# Ionic_Skin_Sensorized_Glove.net
KiCad netlist of a schematic drawn in EAGLE
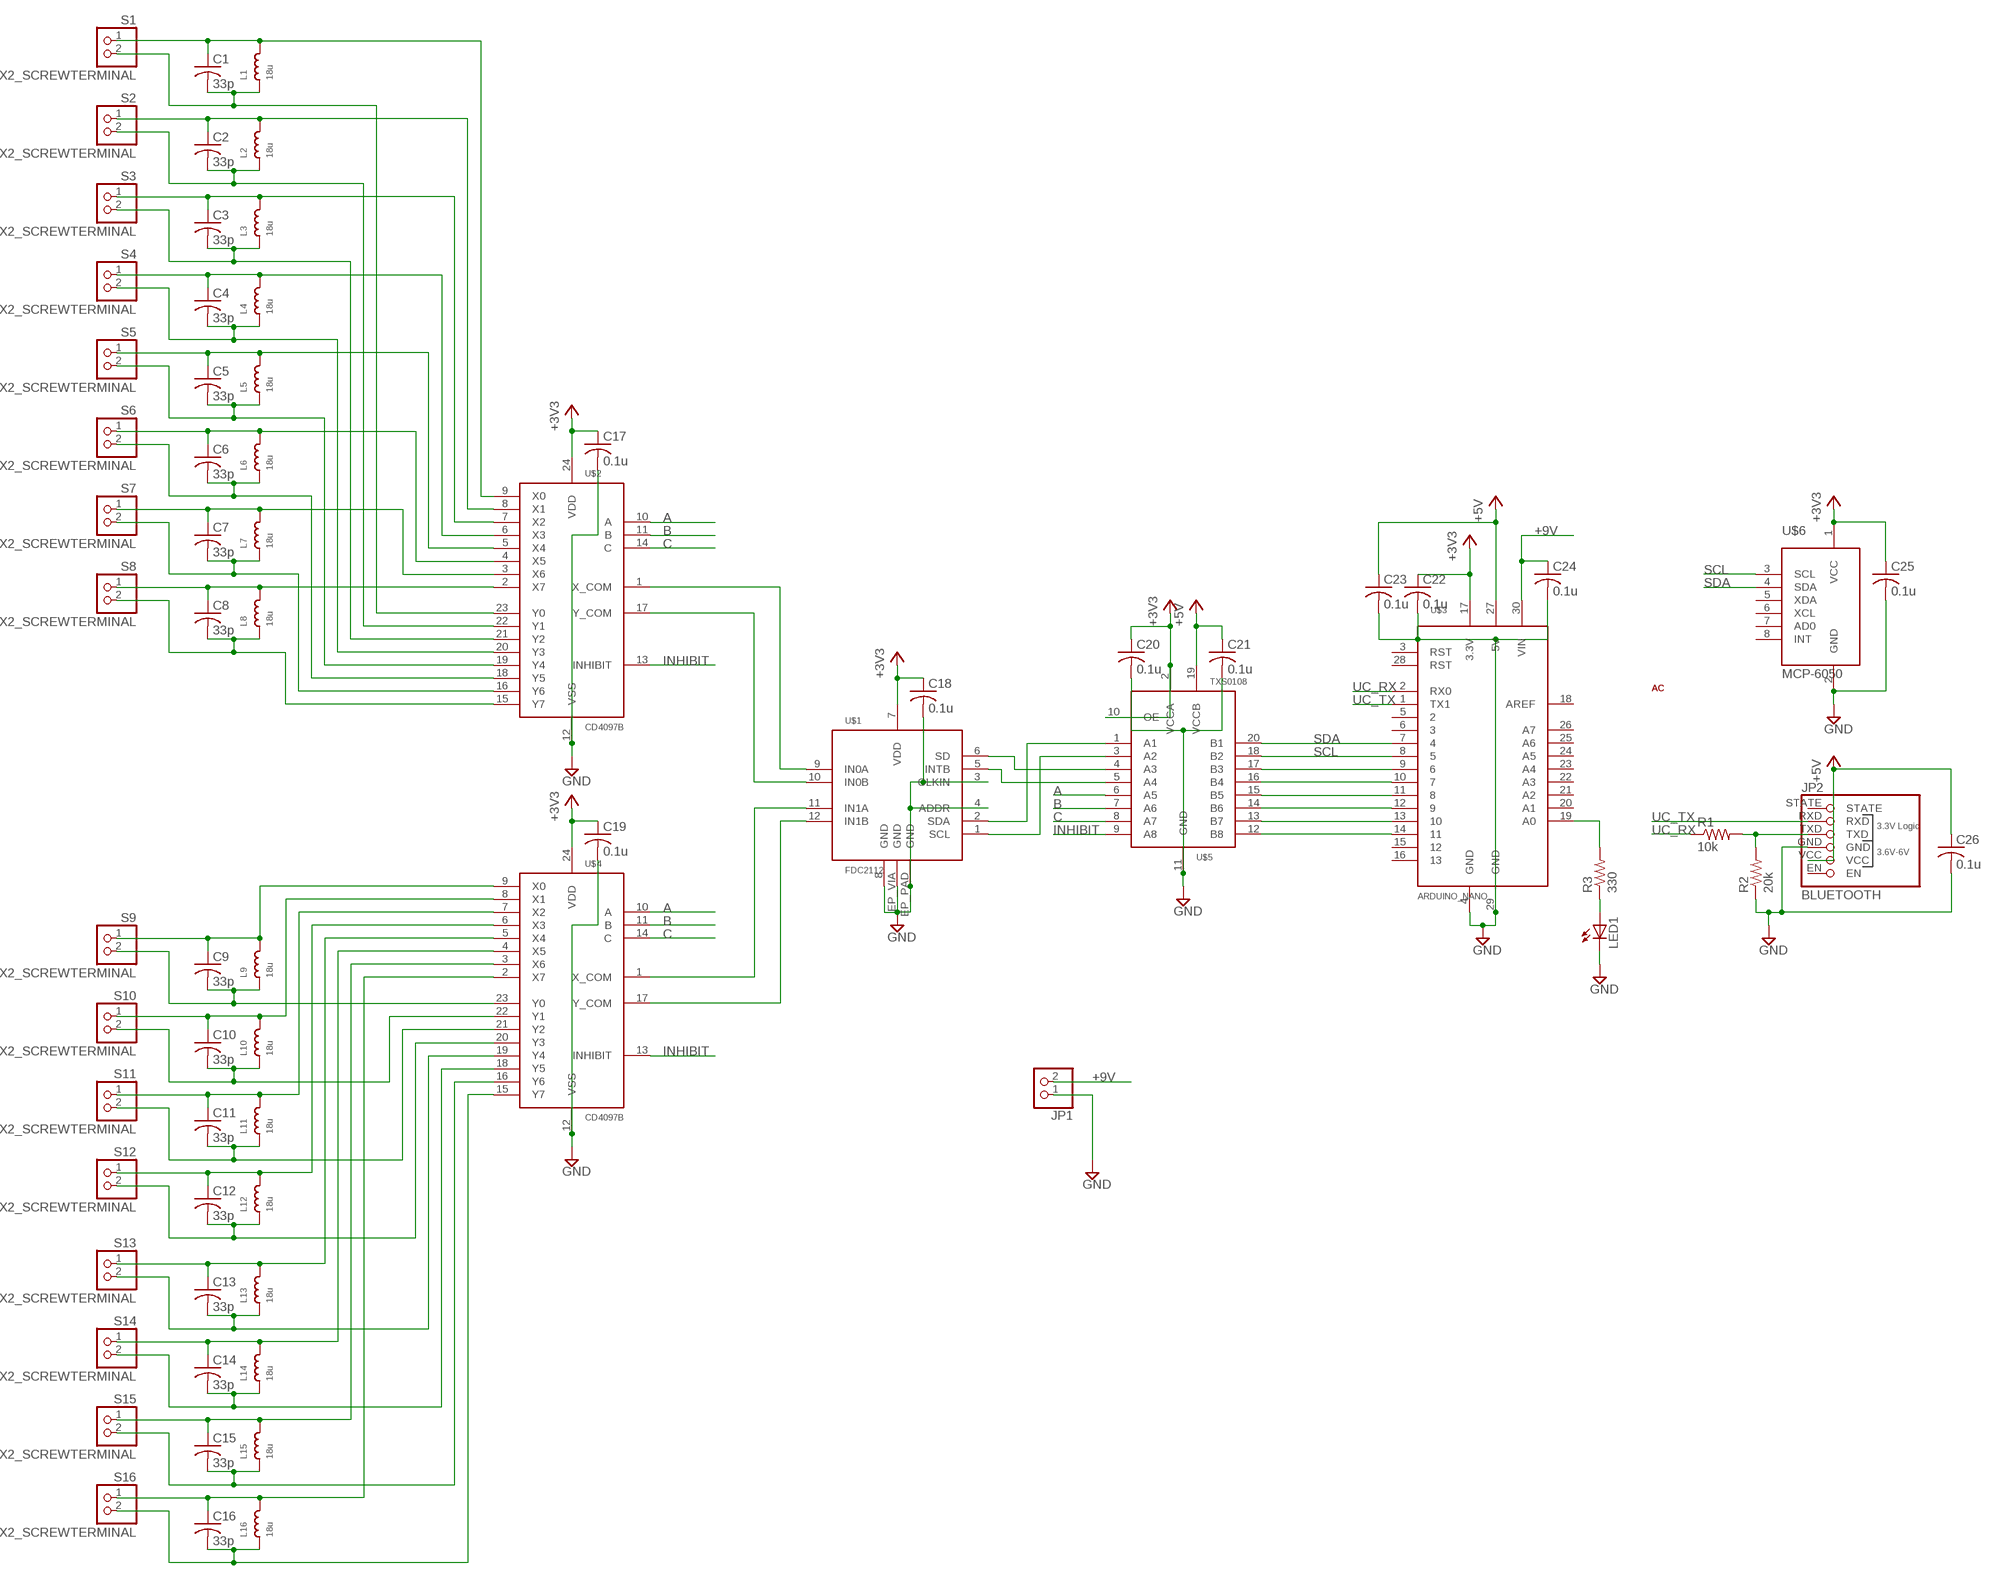
[diagram p0: schematic, sheet 1]

(export (version "E")
  (design (tool "Eeschema 10.0.6"))
  (components
    (comp (ref "C1")
      (value "33p")
      (footprint "eagle-import:C0805")
      (libsource (lib "eagle-import") (part "C-USC0805"))
    )
    (comp (ref "C2")
      (value "33p")
      (footprint "eagle-import:C0805")
      (libsource (lib "eagle-import") (part "C-USC0805"))
    )
    (comp (ref "C3")
      (value "33p")
      (footprint "eagle-import:C0805")
      (libsource (lib "eagle-import") (part "C-USC0805"))
    )
    (comp (ref "C4")
      (value "33p")
      (footprint "eagle-import:C0805")
      (libsource (lib "eagle-import") (part "C-USC0805"))
    )
    (comp (ref "C5")
      (value "33p")
      (footprint "eagle-import:C0805")
      (libsource (lib "eagle-import") (part "C-USC0805"))
    )
    (comp (ref "C6")
      (value "33p")
      (footprint "eagle-import:C0805")
      (libsource (lib "eagle-import") (part "C-USC0805"))
    )
    (comp (ref "C7")
      (value "33p")
      (footprint "eagle-import:C0805")
      (libsource (lib "eagle-import") (part "C-USC0805"))
    )
    (comp (ref "C8")
      (value "33p")
      (footprint "eagle-import:C0805")
      (libsource (lib "eagle-import") (part "C-USC0805"))
    )
    (comp (ref "C9")
      (value "33p")
      (footprint "eagle-import:C0805")
      (libsource (lib "eagle-import") (part "C-USC0805"))
    )
    (comp (ref "C10")
      (value "33p")
      (footprint "eagle-import:C0805")
      (libsource (lib "eagle-import") (part "C-USC0805"))
    )
    (comp (ref "C11")
      (value "33p")
      (footprint "eagle-import:C0805")
      (libsource (lib "eagle-import") (part "C-USC0805"))
    )
    (comp (ref "C12")
      (value "33p")
      (footprint "eagle-import:C0805")
      (libsource (lib "eagle-import") (part "C-USC0805"))
    )
    (comp (ref "C13")
      (value "33p")
      (footprint "eagle-import:C0805")
      (libsource (lib "eagle-import") (part "C-USC0805"))
    )
    (comp (ref "C14")
      (value "33p")
      (footprint "eagle-import:C0805")
      (libsource (lib "eagle-import") (part "C-USC0805"))
    )
    (comp (ref "C15")
      (value "33p")
      (footprint "eagle-import:C0805")
      (libsource (lib "eagle-import") (part "C-USC0805"))
    )
    (comp (ref "C16")
      (value "33p")
      (footprint "eagle-import:C0805")
      (libsource (lib "eagle-import") (part "C-USC0805"))
    )
    (comp (ref "C17")
      (value "0.1u")
      (footprint "eagle-import:C0805")
      (libsource (lib "eagle-import") (part "C-USC0805"))
    )
    (comp (ref "C18")
      (value "0.1u")
      (footprint "eagle-import:C0805")
      (libsource (lib "eagle-import") (part "C-USC0805"))
    )
    (comp (ref "C19")
      (value "0.1u")
      (footprint "eagle-import:C0805")
      (libsource (lib "eagle-import") (part "C-USC0805"))
    )
    (comp (ref "C20")
      (value "0.1u")
      (footprint "eagle-import:C0805")
      (libsource (lib "eagle-import") (part "C-USC0805"))
    )
    (comp (ref "C21")
      (value "0.1u")
      (footprint "eagle-import:C0805")
      (libsource (lib "eagle-import") (part "C-USC0805"))
    )
    (comp (ref "C22")
      (value "0.1u")
      (footprint "eagle-import:C0805")
      (libsource (lib "eagle-import") (part "C-USC0805"))
    )
    (comp (ref "C23")
      (value "0.1u")
      (footprint "eagle-import:C0805")
      (libsource (lib "eagle-import") (part "C-USC0805"))
    )
    (comp (ref "C24")
      (value "0.1u")
      (footprint "eagle-import:C0805")
      (libsource (lib "eagle-import") (part "C-USC0805"))
    )
    (comp (ref "C25")
      (value "0.1u")
      (footprint "eagle-import:C0805")
      (libsource (lib "eagle-import") (part "C-USC0805"))
    )
    (comp (ref "C26")
      (value "0.1u")
      (footprint "eagle-import:C0805")
      (libsource (lib "eagle-import") (part "C-USC0805"))
    )
    (comp (ref "JP1")
      (value "PINHD-1X2")
      (footprint "eagle-import:1X02")
      (libsource (lib "eagle-import") (part "PINHD-1X2"))
    )
    (comp (ref "JP2")
      (value "BLUETOOTH")
      (footprint "eagle-import:HC-06")
      (libsource (lib "eagle-import") (part "HC-06"))
    )
    (comp (ref "L1")
      (value "18u")
      (footprint "eagle-import:_0805MP")
      (libsource (lib "eagle-import") (part "INDUCTOR_0805MP"))
    )
    (comp (ref "L2")
      (value "18u")
      (footprint "eagle-import:_0805MP")
      (libsource (lib "eagle-import") (part "INDUCTOR_0805MP"))
    )
    (comp (ref "L3")
      (value "18u")
      (footprint "eagle-import:_0805MP")
      (libsource (lib "eagle-import") (part "INDUCTOR_0805MP"))
    )
    (comp (ref "L4")
      (value "18u")
      (footprint "eagle-import:_0805MP")
      (libsource (lib "eagle-import") (part "INDUCTOR_0805MP"))
    )
    (comp (ref "L5")
      (value "18u")
      (footprint "eagle-import:_0805MP")
      (libsource (lib "eagle-import") (part "INDUCTOR_0805MP"))
    )
    (comp (ref "L6")
      (value "18u")
      (footprint "eagle-import:_0805MP")
      (libsource (lib "eagle-import") (part "INDUCTOR_0805MP"))
    )
    (comp (ref "L7")
      (value "18u")
      (footprint "eagle-import:_0805MP")
      (libsource (lib "eagle-import") (part "INDUCTOR_0805MP"))
    )
    (comp (ref "L8")
      (value "18u")
      (footprint "eagle-import:_0805MP")
      (libsource (lib "eagle-import") (part "INDUCTOR_0805MP"))
    )
    (comp (ref "L9")
      (value "18u")
      (footprint "eagle-import:_0805MP")
      (libsource (lib "eagle-import") (part "INDUCTOR_0805MP"))
    )
    (comp (ref "L10")
      (value "18u")
      (footprint "eagle-import:_0805MP")
      (libsource (lib "eagle-import") (part "INDUCTOR_0805MP"))
    )
    (comp (ref "L11")
      (value "18u")
      (footprint "eagle-import:_0805MP")
      (libsource (lib "eagle-import") (part "INDUCTOR_0805MP"))
    )
    (comp (ref "L12")
      (value "18u")
      (footprint "eagle-import:_0805MP")
      (libsource (lib "eagle-import") (part "INDUCTOR_0805MP"))
    )
    (comp (ref "L13")
      (value "18u")
      (footprint "eagle-import:_0805MP")
      (libsource (lib "eagle-import") (part "INDUCTOR_0805MP"))
    )
    (comp (ref "L14")
      (value "18u")
      (footprint "eagle-import:_0805MP")
      (libsource (lib "eagle-import") (part "INDUCTOR_0805MP"))
    )
    (comp (ref "L15")
      (value "18u")
      (footprint "eagle-import:_0805MP")
      (libsource (lib "eagle-import") (part "INDUCTOR_0805MP"))
    )
    (comp (ref "L16")
      (value "18u")
      (footprint "eagle-import:_0805MP")
      (libsource (lib "eagle-import") (part "INDUCTOR_0805MP"))
    )
    (comp (ref "LED1")
      (value "LEDCHIPLED_0805")
      (footprint "eagle-import:CHIPLED_0805")
      (libsource (lib "eagle-import") (part "LEDCHIPLED_0805"))
    )
    (comp (ref "R1")
      (value "10k")
      (footprint "eagle-import:R0805")
      (libsource (lib "eagle-import") (part "R-US_R0805"))
    )
    (comp (ref "R2")
      (value "20k")
      (footprint "eagle-import:R0805")
      (libsource (lib "eagle-import") (part "R-US_R0805"))
    )
    (comp (ref "R3")
      (value "330")
      (footprint "eagle-import:R0805")
      (libsource (lib "eagle-import") (part "R-US_R0805"))
    )
    (comp (ref "S1")
      (value "1X2_SCREWTERMINAL")
      (footprint "eagle-import:1X2-2.54MM")
      (libsource (lib "eagle-import") (part "1X2_SCREWTERMINAL"))
    )
    (comp (ref "S2")
      (value "1X2_SCREWTERMINAL")
      (footprint "eagle-import:1X2-2.54MM")
      (libsource (lib "eagle-import") (part "1X2_SCREWTERMINAL"))
    )
    (comp (ref "S3")
      (value "1X2_SCREWTERMINAL")
      (footprint "eagle-import:1X2-2.54MM")
      (libsource (lib "eagle-import") (part "1X2_SCREWTERMINAL"))
    )
    (comp (ref "S4")
      (value "1X2_SCREWTERMINAL")
      (footprint "eagle-import:1X2-2.54MM")
      (libsource (lib "eagle-import") (part "1X2_SCREWTERMINAL"))
    )
    (comp (ref "S5")
      (value "1X2_SCREWTERMINAL")
      (footprint "eagle-import:1X2-2.54MM")
      (libsource (lib "eagle-import") (part "1X2_SCREWTERMINAL"))
    )
    (comp (ref "S6")
      (value "1X2_SCREWTERMINAL")
      (footprint "eagle-import:1X2-2.54MM")
      (libsource (lib "eagle-import") (part "1X2_SCREWTERMINAL"))
    )
    (comp (ref "S7")
      (value "1X2_SCREWTERMINAL")
      (footprint "eagle-import:1X2-2.54MM")
      (libsource (lib "eagle-import") (part "1X2_SCREWTERMINAL"))
    )
    (comp (ref "S8")
      (value "1X2_SCREWTERMINAL")
      (footprint "eagle-import:1X2-2.54MM")
      (libsource (lib "eagle-import") (part "1X2_SCREWTERMINAL"))
    )
    (comp (ref "S9")
      (value "1X2_SCREWTERMINAL")
      (footprint "eagle-import:1X2-2.54MM")
      (libsource (lib "eagle-import") (part "1X2_SCREWTERMINAL"))
    )
    (comp (ref "S10")
      (value "1X2_SCREWTERMINAL")
      (footprint "eagle-import:1X2-2.54MM")
      (libsource (lib "eagle-import") (part "1X2_SCREWTERMINAL"))
    )
    (comp (ref "S11")
      (value "1X2_SCREWTERMINAL")
      (footprint "eagle-import:1X2-2.54MM")
      (libsource (lib "eagle-import") (part "1X2_SCREWTERMINAL"))
    )
    (comp (ref "S12")
      (value "1X2_SCREWTERMINAL")
      (footprint "eagle-import:1X2-2.54MM")
      (libsource (lib "eagle-import") (part "1X2_SCREWTERMINAL"))
    )
    (comp (ref "S13")
      (value "1X2_SCREWTERMINAL")
      (footprint "eagle-import:1X2-2.54MM")
      (libsource (lib "eagle-import") (part "1X2_SCREWTERMINAL"))
    )
    (comp (ref "S14")
      (value "1X2_SCREWTERMINAL")
      (footprint "eagle-import:1X2-2.54MM")
      (libsource (lib "eagle-import") (part "1X2_SCREWTERMINAL"))
    )
    (comp (ref "S15")
      (value "1X2_SCREWTERMINAL")
      (footprint "eagle-import:1X2-2.54MM")
      (libsource (lib "eagle-import") (part "1X2_SCREWTERMINAL"))
    )
    (comp (ref "S16")
      (value "1X2_SCREWTERMINAL")
      (footprint "eagle-import:1X2-2.54MM")
      (libsource (lib "eagle-import") (part "1X2_SCREWTERMINAL"))
    )
    (comp (ref "U$1")
      (value "FDC2112")
      (footprint "eagle-import:WSON-12")
      (libsource (lib "eagle-import") (part "FDC2112"))
    )
    (comp (ref "U$2")
      (value "CD4097B")
      (footprint "eagle-import:TSSOP-24")
      (libsource (lib "eagle-import") (part "CD4097B"))
    )
    (comp (ref "U$3")
      (value "ARDUINO_NANO")
      (footprint "eagle-import:ARDUINO_NANO")
      (libsource (lib "eagle-import") (part "ARDUINO_NANO"))
    )
    (comp (ref "U$4")
      (value "CD4097B")
      (footprint "eagle-import:TSSOP-24")
      (libsource (lib "eagle-import") (part "CD4097B"))
    )
    (comp (ref "U$5")
      (value "TXS0108")
      (footprint "eagle-import:TSSOP-20")
      (libsource (lib "eagle-import") (part "TXS0108"))
    )
    (comp (ref "U$6")
      (value "MCP-6050")
      (footprint "eagle-import:MCP-6050_BREAKOUT")
      (libsource (lib "eagle-import") (part "MCP-6050"))
    )
    (comp (ref "U$7")
      (value "AC_TOP")
      (footprint "eagle-import:AC_TOP")
      (libsource (lib "eagle-import") (part "AC_TOP"))
    )
    (comp (ref "U$8")
      (value "AC_BOTTOM")
      (footprint "eagle-import:AC_BOTTOM")
      (libsource (lib "eagle-import") (part "AC_BOTTOM"))
    )
  )
  (nets
    (net (code "1") (name "+3V3") (class "Default")
      (node (ref "C17") (pin "1") (pinfunction "1_1") (pintype "passive"))
      (node (ref "C18") (pin "1") (pinfunction "1_1") (pintype "passive"))
      (node (ref "C19") (pin "1") (pinfunction "1_1") (pintype "passive"))
      (node (ref "C20") (pin "1") (pinfunction "1_1") (pintype "passive"))
      (node (ref "C22") (pin "1") (pinfunction "1_1") (pintype "passive"))
      (node (ref "C25") (pin "1") (pinfunction "1_1") (pintype "passive"))
      (node (ref "U$1") (pin "7") (pinfunction "VDD_7") (pintype "power_in"))
      (node (ref "U$2") (pin "24") (pinfunction "VDD_24") (pintype "bidirectional"))
      (node (ref "U$3") (pin "17") (pinfunction "3.3V_17") (pintype "bidirectional"))
      (node (ref "U$4") (pin "24") (pinfunction "VDD_24") (pintype "bidirectional"))
      (node (ref "U$5") (pin "10") (pinfunction "OE_10") (pintype "bidirectional"))
      (node (ref "U$5") (pin "2") (pinfunction "VCCA_2") (pintype "bidirectional"))
      (node (ref "U$6") (pin "1") (pinfunction "VCC_1") (pintype "bidirectional"))
    )
    (net (code "2") (name "+5V") (class "Default")
      (node (ref "C21") (pin "1") (pinfunction "1_1") (pintype "passive"))
      (node (ref "C23") (pin "1") (pinfunction "1_1") (pintype "passive"))
      (node (ref "C26") (pin "1") (pinfunction "1_1") (pintype "passive"))
      (node (ref "JP2") (pin "VCC") (pinfunction "VCC_VCC") (pintype "bidirectional"))
      (node (ref "U$3") (pin "27") (pinfunction "5V_27") (pintype "bidirectional"))
      (node (ref "U$5") (pin "19") (pinfunction "VCCB_19") (pintype "bidirectional"))
    )
    (net (code "3") (name "/+9V") (class "Default")
      (node (ref "C24") (pin "1") (pinfunction "1_1") (pintype "passive"))
      (node (ref "JP1") (pin "2") (pinfunction "2_2") (pintype "passive"))
      (node (ref "U$3") (pin "30") (pinfunction "VIN_30") (pintype "bidirectional"))
    )
    (net (code "4") (name "/A") (class "Default")
      (node (ref "U$2") (pin "10") (pinfunction "A_10") (pintype "bidirectional"))
      (node (ref "U$4") (pin "10") (pinfunction "A_10") (pintype "bidirectional"))
      (node (ref "U$5") (pin "6") (pinfunction "A5_6") (pintype "bidirectional"))
    )
    (net (code "5") (name "/B") (class "Default")
      (node (ref "U$2") (pin "11") (pinfunction "B_11") (pintype "bidirectional"))
      (node (ref "U$4") (pin "11") (pinfunction "B_11") (pintype "bidirectional"))
      (node (ref "U$5") (pin "7") (pinfunction "A6_7") (pintype "bidirectional"))
    )
    (net (code "6") (name "/C") (class "Default")
      (node (ref "U$2") (pin "14") (pinfunction "C_14") (pintype "bidirectional"))
      (node (ref "U$4") (pin "14") (pinfunction "C_14") (pintype "bidirectional"))
      (node (ref "U$5") (pin "8") (pinfunction "A7_8") (pintype "bidirectional"))
    )
    (net (code "7") (name "/INHIBIT") (class "Default")
      (node (ref "U$2") (pin "13") (pinfunction "INHIBIT_13") (pintype "bidirectional"))
      (node (ref "U$4") (pin "13") (pinfunction "INHIBIT_13") (pintype "bidirectional"))
      (node (ref "U$5") (pin "9") (pinfunction "A8_9") (pintype "bidirectional"))
    )
    (net (code "8") (name "/SCL") (class "Default")
      (node (ref "U$3") (pin "8") (pinfunction "5_8") (pintype "bidirectional"))
      (node (ref "U$5") (pin "18") (pinfunction "B2_18") (pintype "bidirectional"))
      (node (ref "U$6") (pin "3") (pinfunction "SCL_3") (pintype "bidirectional"))
    )
    (net (code "9") (name "/SDA") (class "Default")
      (node (ref "U$3") (pin "7") (pinfunction "4_7") (pintype "bidirectional"))
      (node (ref "U$5") (pin "20") (pinfunction "B1_20") (pintype "bidirectional"))
      (node (ref "U$6") (pin "4") (pinfunction "SDA_4") (pintype "bidirectional"))
    )
    (net (code "10") (name "/UC_RX") (class "Default")
      (node (ref "R1") (pin "1") (pinfunction "1_1") (pintype "passive"))
      (node (ref "U$3") (pin "2") (pinfunction "RX0_2") (pintype "bidirectional"))
    )
    (net (code "11") (name "/UC_TX") (class "Default")
      (node (ref "JP2") (pin "RXD") (pinfunction "RXD_RXD") (pintype "bidirectional"))
      (node (ref "U$3") (pin "1") (pinfunction "TX1_1") (pintype "bidirectional"))
    )
    (net (code "12") (name "GND") (class "Default")
      (node (ref "C17") (pin "2") (pinfunction "2_2") (pintype "passive"))
      (node (ref "C18") (pin "2") (pinfunction "2_2") (pintype "passive"))
      (node (ref "C19") (pin "2") (pinfunction "2_2") (pintype "passive"))
      (node (ref "C20") (pin "2") (pinfunction "2_2") (pintype "passive"))
      (node (ref "C21") (pin "2") (pinfunction "2_2") (pintype "passive"))
      (node (ref "C22") (pin "2") (pinfunction "2_2") (pintype "passive"))
      (node (ref "C23") (pin "2") (pinfunction "2_2") (pintype "passive"))
      (node (ref "C24") (pin "2") (pinfunction "2_2") (pintype "passive"))
      (node (ref "C25") (pin "2") (pinfunction "2_2") (pintype "passive"))
      (node (ref "C26") (pin "2") (pinfunction "2_2") (pintype "passive"))
      (node (ref "JP1") (pin "1") (pinfunction "1_1") (pintype "passive"))
      (node (ref "JP2") (pin "GND") (pinfunction "GND_GND") (pintype "bidirectional"))
      (node (ref "LED1") (pin "C") (pinfunction "C_C") (pintype "passive"))
      (node (ref "R2") (pin "1") (pinfunction "1_1") (pintype "passive"))
      (node (ref "U$1") (pin "3") (pinfunction "CLKIN_3") (pintype "bidirectional"))
      (node (ref "U$1") (pin "4") (pinfunction "ADDR_4") (pintype "bidirectional"))
      (node (ref "U$1") (pin "8") (pinfunction "GND_8") (pintype "power_in"))
      (node (ref "U$1") (pin "EP_PAD") (pinfunction "GND_EP_PAD") (pintype "bidirectional"))
      (node (ref "U$1") (pin "EP_VIA") (pinfunction "GND_EP_VIA") (pintype "bidirectional"))
      (node (ref "U$2") (pin "12") (pinfunction "VSS_12") (pintype "bidirectional"))
      (node (ref "U$3") (pin "29") (pinfunction "GND_29") (pintype "bidirectional"))
      (node (ref "U$3") (pin "4") (pinfunction "GND_4") (pintype "bidirectional"))
      (node (ref "U$4") (pin "12") (pinfunction "VSS_12") (pintype "bidirectional"))
      (node (ref "U$5") (pin "11") (pinfunction "GND_11") (pintype "bidirectional"))
      (node (ref "U$6") (pin "2") (pinfunction "GND_2") (pintype "bidirectional"))
    )
    (net (code "13") (name "Net-(JP2-PadTXD)") (class "Default")
      (node (ref "JP2") (pin "TXD") (pinfunction "TXD_TXD") (pintype "bidirectional"))
      (node (ref "R1") (pin "2") (pinfunction "2_2") (pintype "passive"))
      (node (ref "R2") (pin "2") (pinfunction "2_2") (pintype "passive"))
    )
    (net (code "14") (name "Net-(LED1-PadA)") (class "Default")
      (node (ref "LED1") (pin "A") (pinfunction "A_A") (pintype "passive"))
      (node (ref "R3") (pin "1") (pinfunction "1_1") (pintype "passive"))
    )
    (net (code "15") (name "Net-(U$1-IN0A)") (class "Default")
      (node (ref "U$1") (pin "9") (pinfunction "IN0A_9") (pintype "bidirectional"))
      (node (ref "U$2") (pin "1") (pinfunction "X_COM_1") (pintype "bidirectional"))
    )
    (net (code "16") (name "Net-(U$1-IN0B)") (class "Default")
      (node (ref "U$1") (pin "10") (pinfunction "IN0B_10") (pintype "bidirectional"))
      (node (ref "U$2") (pin "17") (pinfunction "Y_COM_17") (pintype "bidirectional"))
    )
    (net (code "17") (name "Net-(U$1-IN1A)") (class "Default")
      (node (ref "U$1") (pin "11") (pinfunction "IN1A_11") (pintype "bidirectional"))
      (node (ref "U$4") (pin "1") (pinfunction "X_COM_1") (pintype "bidirectional"))
    )
    (net (code "18") (name "Net-(U$1-IN1B)") (class "Default")
      (node (ref "U$1") (pin "12") (pinfunction "IN1B_12") (pintype "bidirectional"))
      (node (ref "U$4") (pin "17") (pinfunction "Y_COM_17") (pintype "bidirectional"))
    )
    (net (code "19") (name "Net-(U$1-INTB)") (class "Default")
      (node (ref "U$1") (pin "5") (pinfunction "INTB_5") (pintype "bidirectional"))
      (node (ref "U$5") (pin "5") (pinfunction "A4_5") (pintype "bidirectional"))
    )
    (net (code "20") (name "Net-(U$1-SCL)") (class "Default")
      (node (ref "U$1") (pin "1") (pinfunction "SCL_1") (pintype "bidirectional"))
      (node (ref "U$5") (pin "3") (pinfunction "A2_3") (pintype "bidirectional"))
    )
    (net (code "21") (name "Net-(U$1-SD)") (class "Default")
      (node (ref "U$1") (pin "6") (pinfunction "SD_6") (pintype "bidirectional"))
      (node (ref "U$5") (pin "4") (pinfunction "A3_4") (pintype "bidirectional"))
    )
    (net (code "22") (name "Net-(U$1-SDA)") (class "Default")
      (node (ref "U$1") (pin "2") (pinfunction "SDA_2") (pintype "bidirectional"))
      (node (ref "U$5") (pin "1") (pinfunction "A1_1") (pintype "bidirectional"))
    )
    (net (code "23") (name "Net-(U$2-X0)") (class "Default")
      (node (ref "C1") (pin "1") (pinfunction "1_1") (pintype "passive"))
      (node (ref "L1") (pin "2") (pinfunction "2_2") (pintype "passive"))
      (node (ref "S1") (pin "1") (pinfunction "1_1") (pintype "passive"))
      (node (ref "U$2") (pin "9") (pinfunction "X0_9") (pintype "bidirectional"))
    )
    (net (code "24") (name "Net-(U$2-X1)") (class "Default")
      (node (ref "C2") (pin "1") (pinfunction "1_1") (pintype "passive"))
      (node (ref "L2") (pin "2") (pinfunction "2_2") (pintype "passive"))
      (node (ref "S2") (pin "1") (pinfunction "1_1") (pintype "passive"))
      (node (ref "U$2") (pin "8") (pinfunction "X1_8") (pintype "bidirectional"))
    )
    (net (code "25") (name "Net-(U$2-X2)") (class "Default")
      (node (ref "C3") (pin "1") (pinfunction "1_1") (pintype "passive"))
      (node (ref "L3") (pin "2") (pinfunction "2_2") (pintype "passive"))
      (node (ref "S3") (pin "1") (pinfunction "1_1") (pintype "passive"))
      (node (ref "U$2") (pin "7") (pinfunction "X2_7") (pintype "bidirectional"))
    )
    (net (code "26") (name "Net-(U$2-X3)") (class "Default")
      (node (ref "C4") (pin "1") (pinfunction "1_1") (pintype "passive"))
      (node (ref "L4") (pin "2") (pinfunction "2_2") (pintype "passive"))
      (node (ref "S4") (pin "1") (pinfunction "1_1") (pintype "passive"))
      (node (ref "U$2") (pin "6") (pinfunction "X3_6") (pintype "bidirectional"))
    )
    (net (code "27") (name "Net-(U$2-X4)") (class "Default")
      (node (ref "C5") (pin "1") (pinfunction "1_1") (pintype "passive"))
      (node (ref "L5") (pin "2") (pinfunction "2_2") (pintype "passive"))
      (node (ref "S5") (pin "1") (pinfunction "1_1") (pintype "passive"))
      (node (ref "U$2") (pin "5") (pinfunction "X4_5") (pintype "bidirectional"))
    )
    (net (code "28") (name "Net-(U$2-X5)") (class "Default")
      (node (ref "C6") (pin "1") (pinfunction "1_1") (pintype "passive"))
      (node (ref "L6") (pin "2") (pinfunction "2_2") (pintype "passive"))
      (node (ref "S6") (pin "1") (pinfunction "1_1") (pintype "passive"))
      (node (ref "U$2") (pin "4") (pinfunction "X5_4") (pintype "bidirectional"))
    )
    (net (code "29") (name "Net-(U$2-X6)") (class "Default")
      (node (ref "C7") (pin "1") (pinfunction "1_1") (pintype "passive"))
      (node (ref "L7") (pin "2") (pinfunction "2_2") (pintype "passive"))
      (node (ref "S7") (pin "1") (pinfunction "1_1") (pintype "passive"))
      (node (ref "U$2") (pin "3") (pinfunction "X6_3") (pintype "bidirectional"))
    )
    (net (code "30") (name "Net-(U$2-X7)") (class "Default")
      (node (ref "C8") (pin "1") (pinfunction "1_1") (pintype "passive"))
      (node (ref "L8") (pin "2") (pinfunction "2_2") (pintype "passive"))
      (node (ref "S8") (pin "1") (pinfunction "1_1") (pintype "passive"))
      (node (ref "U$2") (pin "2") (pinfunction "X7_2") (pintype "bidirectional"))
    )
    (net (code "31") (name "Net-(U$2-Y0)") (class "Default")
      (node (ref "C1") (pin "2") (pinfunction "2_2") (pintype "passive"))
      (node (ref "L1") (pin "1") (pinfunction "1_1") (pintype "passive"))
      (node (ref "S1") (pin "2") (pinfunction "2_2") (pintype "passive"))
      (node (ref "U$2") (pin "23") (pinfunction "Y0_23") (pintype "bidirectional"))
    )
    (net (code "32") (name "Net-(U$2-Y1)") (class "Default")
      (node (ref "C2") (pin "2") (pinfunction "2_2") (pintype "passive"))
      (node (ref "L2") (pin "1") (pinfunction "1_1") (pintype "passive"))
      (node (ref "S2") (pin "2") (pinfunction "2_2") (pintype "passive"))
      (node (ref "U$2") (pin "22") (pinfunction "Y1_22") (pintype "bidirectional"))
    )
    (net (code "33") (name "Net-(U$2-Y2)") (class "Default")
      (node (ref "C3") (pin "2") (pinfunction "2_2") (pintype "passive"))
      (node (ref "L3") (pin "1") (pinfunction "1_1") (pintype "passive"))
      (node (ref "S3") (pin "2") (pinfunction "2_2") (pintype "passive"))
      (node (ref "U$2") (pin "21") (pinfunction "Y2_21") (pintype "bidirectional"))
    )
    (net (code "34") (name "Net-(U$2-Y3)") (class "Default")
      (node (ref "C4") (pin "2") (pinfunction "2_2") (pintype "passive"))
      (node (ref "L4") (pin "1") (pinfunction "1_1") (pintype "passive"))
      (node (ref "S4") (pin "2") (pinfunction "2_2") (pintype "passive"))
      (node (ref "U$2") (pin "20") (pinfunction "Y3_20") (pintype "bidirectional"))
    )
    (net (code "35") (name "Net-(U$2-Y4)") (class "Default")
      (node (ref "C5") (pin "2") (pinfunction "2_2") (pintype "passive"))
      (node (ref "L5") (pin "1") (pinfunction "1_1") (pintype "passive"))
      (node (ref "S5") (pin "2") (pinfunction "2_2") (pintype "passive"))
      (node (ref "U$2") (pin "19") (pinfunction "Y4_19") (pintype "bidirectional"))
    )
    (net (code "36") (name "Net-(U$2-Y5)") (class "Default")
      (node (ref "C6") (pin "2") (pinfunction "2_2") (pintype "passive"))
      (node (ref "L6") (pin "1") (pinfunction "1_1") (pintype "passive"))
      (node (ref "S6") (pin "2") (pinfunction "2_2") (pintype "passive"))
      (node (ref "U$2") (pin "18") (pinfunction "Y5_18") (pintype "bidirectional"))
    )
    (net (code "37") (name "Net-(U$2-Y6)") (class "Default")
      (node (ref "C7") (pin "2") (pinfunction "2_2") (pintype "passive"))
      (node (ref "L7") (pin "1") (pinfunction "1_1") (pintype "passive"))
      (node (ref "S7") (pin "2") (pinfunction "2_2") (pintype "passive"))
      (node (ref "U$2") (pin "16") (pinfunction "Y6_16") (pintype "bidirectional"))
    )
    (net (code "38") (name "Net-(U$2-Y7)") (class "Default")
      (node (ref "C8") (pin "2") (pinfunction "2_2") (pintype "passive"))
      (node (ref "L8") (pin "1") (pinfunction "1_1") (pintype "passive"))
      (node (ref "S8") (pin "2") (pinfunction "2_2") (pintype "passive"))
      (node (ref "U$2") (pin "15") (pinfunction "Y7_15") (pintype "bidirectional"))
    )
    (net (code "39") (name "Net-(U$3-6)") (class "Default")
      (node (ref "U$3") (pin "9") (pinfunction "6_9") (pintype "bidirectional"))
      (node (ref "U$5") (pin "17") (pinfunction "B3_17") (pintype "bidirectional"))
    )
    (net (code "40") (name "Net-(U$3-7)") (class "Default")
      (node (ref "U$3") (pin "10") (pinfunction "7_10") (pintype "bidirectional"))
      (node (ref "U$5") (pin "16") (pinfunction "B4_16") (pintype "bidirectional"))
    )
    (net (code "41") (name "Net-(U$3-8)") (class "Default")
      (node (ref "U$3") (pin "11") (pinfunction "8_11") (pintype "bidirectional"))
      (node (ref "U$5") (pin "15") (pinfunction "B5_15") (pintype "bidirectional"))
    )
    (net (code "42") (name "Net-(U$3-9)") (class "Default")
      (node (ref "U$3") (pin "12") (pinfunction "9_12") (pintype "bidirectional"))
      (node (ref "U$5") (pin "14") (pinfunction "B6_14") (pintype "bidirectional"))
    )
    (net (code "43") (name "Net-(U$3-10)") (class "Default")
      (node (ref "U$3") (pin "13") (pinfunction "10_13") (pintype "bidirectional"))
      (node (ref "U$5") (pin "13") (pinfunction "B7_13") (pintype "bidirectional"))
    )
    (net (code "44") (name "Net-(U$3-11)") (class "Default")
      (node (ref "U$3") (pin "14") (pinfunction "11_14") (pintype "bidirectional"))
      (node (ref "U$5") (pin "12") (pinfunction "B8_12") (pintype "bidirectional"))
    )
    (net (code "45") (name "Net-(U$3-A0)") (class "Default")
      (node (ref "R3") (pin "2") (pinfunction "2_2") (pintype "passive"))
      (node (ref "U$3") (pin "19") (pinfunction "A0_19") (pintype "bidirectional"))
    )
    (net (code "46") (name "Net-(U$4-X0)") (class "Default")
      (node (ref "C9") (pin "1") (pinfunction "1_1") (pintype "passive"))
      (node (ref "L9") (pin "2") (pinfunction "2_2") (pintype "passive"))
      (node (ref "S9") (pin "1") (pinfunction "1_1") (pintype "passive"))
      (node (ref "U$4") (pin "9") (pinfunction "X0_9") (pintype "bidirectional"))
    )
    (net (code "47") (name "Net-(U$4-X1)") (class "Default")
      (node (ref "C10") (pin "1") (pinfunction "1_1") (pintype "passive"))
      (node (ref "L10") (pin "2") (pinfunction "2_2") (pintype "passive"))
      (node (ref "S10") (pin "1") (pinfunction "1_1") (pintype "passive"))
      (node (ref "U$4") (pin "8") (pinfunction "X1_8") (pintype "bidirectional"))
    )
    (net (code "48") (name "Net-(U$4-X2)") (class "Default")
      (node (ref "C11") (pin "1") (pinfunction "1_1") (pintype "passive"))
      (node (ref "L11") (pin "2") (pinfunction "2_2") (pintype "passive"))
      (node (ref "S11") (pin "1") (pinfunction "1_1") (pintype "passive"))
      (node (ref "U$4") (pin "7") (pinfunction "X2_7") (pintype "bidirectional"))
    )
    (net (code "49") (name "Net-(U$4-X3)") (class "Default")
      (node (ref "C12") (pin "1") (pinfunction "1_1") (pintype "passive"))
      (node (ref "L12") (pin "2") (pinfunction "2_2") (pintype "passive"))
      (node (ref "S12") (pin "1") (pinfunction "1_1") (pintype "passive"))
      (node (ref "U$4") (pin "6") (pinfunction "X3_6") (pintype "bidirectional"))
    )
    (net (code "50") (name "Net-(U$4-X4)") (class "Default")
      (node (ref "C13") (pin "1") (pinfunction "1_1") (pintype "passive"))
      (node (ref "L13") (pin "2") (pinfunction "2_2") (pintype "passive"))
      (node (ref "S13") (pin "1") (pinfunction "1_1") (pintype "passive"))
      (node (ref "U$4") (pin "5") (pinfunction "X4_5") (pintype "bidirectional"))
    )
    (net (code "51") (name "Net-(U$4-X5)") (class "Default")
      (node (ref "C14") (pin "1") (pinfunction "1_1") (pintype "passive"))
      (node (ref "L14") (pin "2") (pinfunction "2_2") (pintype "passive"))
      (node (ref "S14") (pin "1") (pinfunction "1_1") (pintype "passive"))
      (node (ref "U$4") (pin "4") (pinfunction "X5_4") (pintype "bidirectional"))
    )
    (net (code "52") (name "Net-(U$4-X6)") (class "Default")
      (node (ref "C15") (pin "1") (pinfunction "1_1") (pintype "passive"))
      (node (ref "L15") (pin "2") (pinfunction "2_2") (pintype "passive"))
      (node (ref "S15") (pin "1") (pinfunction "1_1") (pintype "passive"))
      (node (ref "U$4") (pin "3") (pinfunction "X6_3") (pintype "bidirectional"))
    )
    (net (code "53") (name "Net-(U$4-X7)") (class "Default")
      (node (ref "C16") (pin "1") (pinfunction "1_1") (pintype "passive"))
      (node (ref "L16") (pin "2") (pinfunction "2_2") (pintype "passive"))
      (node (ref "S16") (pin "1") (pinfunction "1_1") (pintype "passive"))
      (node (ref "U$4") (pin "2") (pinfunction "X7_2") (pintype "bidirectional"))
    )
    (net (code "54") (name "Net-(U$4-Y0)") (class "Default")
      (node (ref "C9") (pin "2") (pinfunction "2_2") (pintype "passive"))
      (node (ref "L9") (pin "1") (pinfunction "1_1") (pintype "passive"))
      (node (ref "S9") (pin "2") (pinfunction "2_2") (pintype "passive"))
      (node (ref "U$4") (pin "23") (pinfunction "Y0_23") (pintype "bidirectional"))
    )
    (net (code "55") (name "Net-(U$4-Y1)") (class "Default")
      (node (ref "C10") (pin "2") (pinfunction "2_2") (pintype "passive"))
      (node (ref "L10") (pin "1") (pinfunction "1_1") (pintype "passive"))
      (node (ref "S10") (pin "2") (pinfunction "2_2") (pintype "passive"))
      (node (ref "U$4") (pin "22") (pinfunction "Y1_22") (pintype "bidirectional"))
    )
    (net (code "56") (name "Net-(U$4-Y2)") (class "Default")
      (node (ref "C11") (pin "2") (pinfunction "2_2") (pintype "passive"))
      (node (ref "L11") (pin "1") (pinfunction "1_1") (pintype "passive"))
      (node (ref "S11") (pin "2") (pinfunction "2_2") (pintype "passive"))
      (node (ref "U$4") (pin "21") (pinfunction "Y2_21") (pintype "bidirectional"))
    )
    (net (code "57") (name "Net-(U$4-Y3)") (class "Default")
      (node (ref "C12") (pin "2") (pinfunction "2_2") (pintype "passive"))
      (node (ref "L12") (pin "1") (pinfunction "1_1") (pintype "passive"))
      (node (ref "S12") (pin "2") (pinfunction "2_2") (pintype "passive"))
      (node (ref "U$4") (pin "20") (pinfunction "Y3_20") (pintype "bidirectional"))
    )
    (net (code "58") (name "Net-(U$4-Y4)") (class "Default")
      (node (ref "C13") (pin "2") (pinfunction "2_2") (pintype "passive"))
      (node (ref "L13") (pin "1") (pinfunction "1_1") (pintype "passive"))
      (node (ref "S13") (pin "2") (pinfunction "2_2") (pintype "passive"))
      (node (ref "U$4") (pin "19") (pinfunction "Y4_19") (pintype "bidirectional"))
    )
    (net (code "59") (name "Net-(U$4-Y5)") (class "Default")
      (node (ref "C14") (pin "2") (pinfunction "2_2") (pintype "passive"))
      (node (ref "L14") (pin "1") (pinfunction "1_1") (pintype "passive"))
      (node (ref "S14") (pin "2") (pinfunction "2_2") (pintype "passive"))
      (node (ref "U$4") (pin "18") (pinfunction "Y5_18") (pintype "bidirectional"))
    )
    (net (code "60") (name "Net-(U$4-Y6)") (class "Default")
      (node (ref "C15") (pin "2") (pinfunction "2_2") (pintype "passive"))
      (node (ref "L15") (pin "1") (pinfunction "1_1") (pintype "passive"))
      (node (ref "S15") (pin "2") (pinfunction "2_2") (pintype "passive"))
      (node (ref "U$4") (pin "16") (pinfunction "Y6_16") (pintype "bidirectional"))
    )
    (net (code "61") (name "Net-(U$4-Y7)") (class "Default")
      (node (ref "C16") (pin "2") (pinfunction "2_2") (pintype "passive"))
      (node (ref "L16") (pin "1") (pinfunction "1_1") (pintype "passive"))
      (node (ref "S16") (pin "2") (pinfunction "2_2") (pintype "passive"))
      (node (ref "U$4") (pin "15") (pinfunction "Y7_15") (pintype "bidirectional"))
    )
    (net (code "62") (name "unconnected-(JP2-PadEN)") (class "Default")
      (node (ref "JP2") (pin "EN") (pinfunction "EN_EN") (pintype "bidirectional"))
    )
    (net (code "63") (name "unconnected-(JP2-PadSTATE)") (class "Default")
      (node (ref "JP2") (pin "STATE") (pinfunction "STATE_STATE") (pintype "bidirectional"))
    )
    (net (code "64") (name "unconnected-(U$3-2-Pad5)") (class "Default")
      (node (ref "U$3") (pin "5") (pinfunction "2_5") (pintype "bidirectional"))
    )
    (net (code "65") (name "unconnected-(U$3-3-Pad6)") (class "Default")
      (node (ref "U$3") (pin "6") (pinfunction "3_6") (pintype "bidirectional"))
    )
    (net (code "66") (name "unconnected-(U$3-12-Pad15)") (class "Default")
      (node (ref "U$3") (pin "15") (pinfunction "12_15") (pintype "bidirectional"))
    )
    (net (code "67") (name "unconnected-(U$3-13-Pad16)") (class "Default")
      (node (ref "U$3") (pin "16") (pinfunction "13_16") (pintype "bidirectional"))
    )
    (net (code "68") (name "unconnected-(U$3-A1-Pad20)") (class "Default")
      (node (ref "U$3") (pin "20") (pinfunction "A1_20") (pintype "bidirectional"))
    )
    (net (code "69") (name "unconnected-(U$3-A2-Pad21)") (class "Default")
      (node (ref "U$3") (pin "21") (pinfunction "A2_21") (pintype "bidirectional"))
    )
    (net (code "70") (name "unconnected-(U$3-A3-Pad22)") (class "Default")
      (node (ref "U$3") (pin "22") (pinfunction "A3_22") (pintype "bidirectional"))
    )
    (net (code "71") (name "unconnected-(U$3-A4-Pad23)") (class "Default")
      (node (ref "U$3") (pin "23") (pinfunction "A4_23") (pintype "bidirectional"))
    )
    (net (code "72") (name "unconnected-(U$3-A5-Pad24)") (class "Default")
      (node (ref "U$3") (pin "24") (pinfunction "A5_24") (pintype "bidirectional"))
    )
    (net (code "73") (name "unconnected-(U$3-A6-Pad25)") (class "Default")
      (node (ref "U$3") (pin "25") (pinfunction "A6_25") (pintype "bidirectional"))
    )
    (net (code "74") (name "unconnected-(U$3-A7-Pad26)") (class "Default")
      (node (ref "U$3") (pin "26") (pinfunction "A7_26") (pintype "bidirectional"))
    )
    (net (code "75") (name "unconnected-(U$3-AREF-Pad18)") (class "Default")
      (node (ref "U$3") (pin "18") (pinfunction "AREF_18") (pintype "bidirectional"))
    )
    (net (code "76") (name "unconnected-(U$3-RST-Pad3)") (class "Default")
      (node (ref "U$3") (pin "3") (pinfunction "RST_3") (pintype "bidirectional"))
    )
    (net (code "77") (name "unconnected-(U$3-RST-Pad28)") (class "Default")
      (node (ref "U$3") (pin "28") (pinfunction "RST_28") (pintype "bidirectional"))
    )
    (net (code "78") (name "unconnected-(U$6-AD0-Pad7)") (class "Default")
      (node (ref "U$6") (pin "7") (pinfunction "AD0_7") (pintype "bidirectional"))
    )
    (net (code "79") (name "unconnected-(U$6-INT-Pad8)") (class "Default")
      (node (ref "U$6") (pin "8") (pinfunction "INT_8") (pintype "bidirectional"))
    )
    (net (code "80") (name "unconnected-(U$6-XCL-Pad6)") (class "Default")
      (node (ref "U$6") (pin "6") (pinfunction "XCL_6") (pintype "bidirectional"))
    )
    (net (code "81") (name "unconnected-(U$6-XDA-Pad5)") (class "Default")
      (node (ref "U$6") (pin "5") (pinfunction "XDA_5") (pintype "bidirectional"))
    )
  )
)
